# ESD_FINAL_SCHEMATICS2.net
KiCad netlist of a schematic drawn in EAGLE
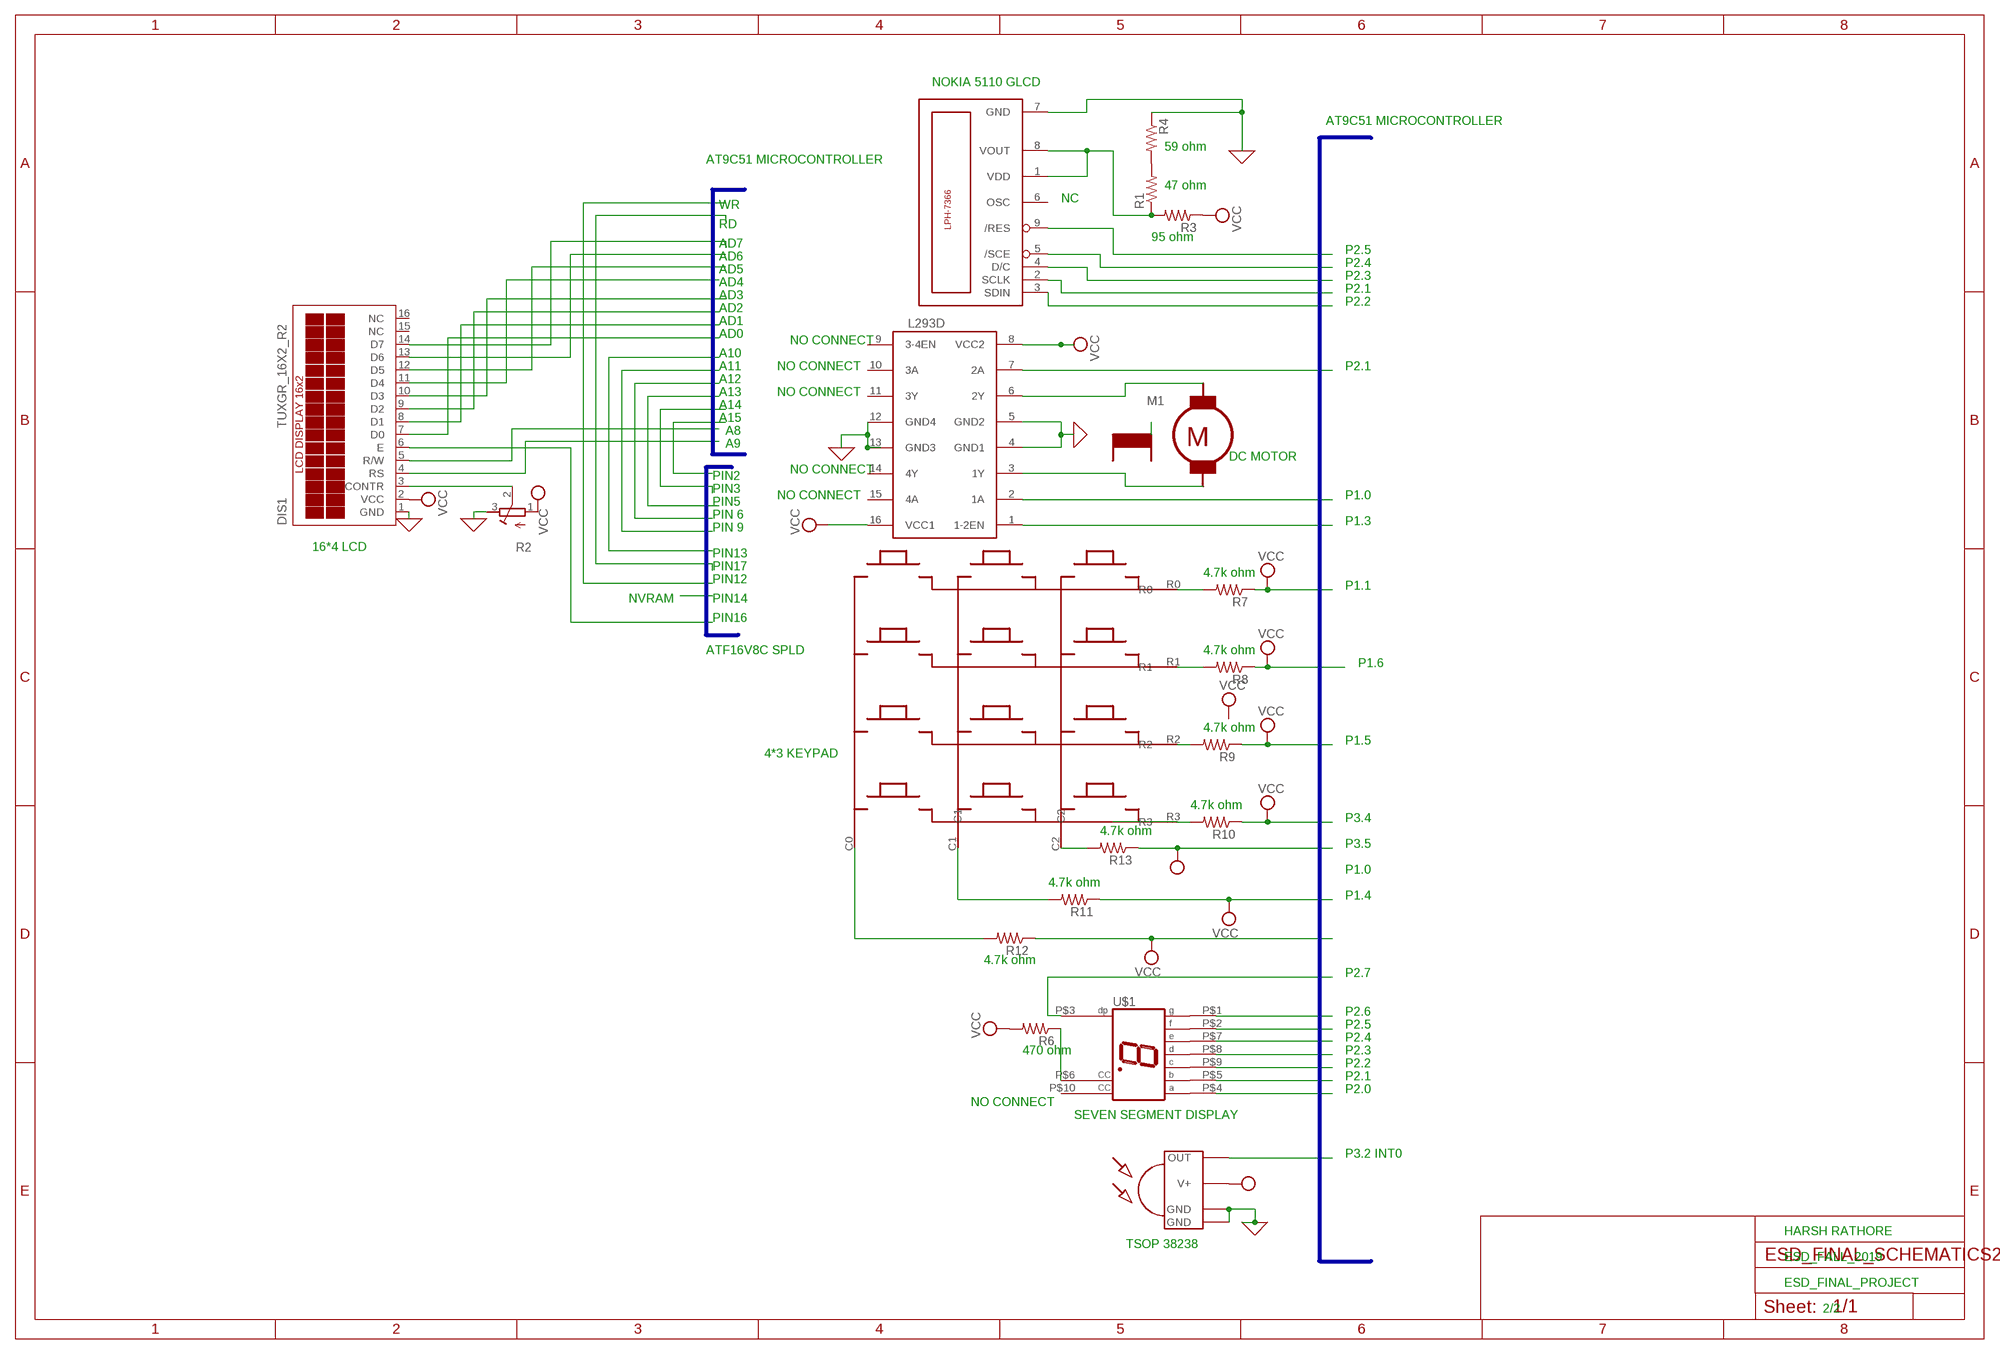
[diagram p0: schematic, sheet 1]

(export (version "E")
  (design (tool "Eeschema 10.0.6"))
  (components
    (comp (ref "DIS1")
      (value "TUXGR_16X2_R2")
      (footprint "eagle-import:TUXGR_16X2_R2")
      (libsource (lib "eagle-import") (part "TUXGR_16X2_R2"))
    )
    (comp (ref "IC1")
      (value "L293D")
      (footprint "eagle-import:DIL16")
      (libsource (lib "eagle-import") (part "L293D"))
    )
    (comp (ref "KP1")
      (value "KEYPAD")
      (footprint "eagle-import:KEYPAD")
      (libsource (lib "eagle-import") (part "KEYPAD"))
    )
    (comp (ref "LCD3")
      (value "LPH-7366")
      (footprint "eagle-import:LPH-7366")
      (libsource (lib "eagle-import") (part "LPH-7366"))
    )
    (comp (ref "M1")
      (value "MOTOR_DC_2_XL")
      (footprint "eagle-import:4PIN")
      (libsource (lib "eagle-import") (part "MOTOR_DC_2_XL"))
    )
    (comp (ref "R1")
      (value "R-US_0204/2V")
      (footprint "eagle-import:0204V")
      (libsource (lib "eagle-import") (part "R-US_0204/2V"))
    )
    (comp (ref "R2")
      (value "R-TRIMM4G/J")
      (footprint "eagle-import:RTRIM4G_J")
      (libsource (lib "eagle-import") (part "R-TRIMM4G/J"))
    )
    (comp (ref "R3")
      (value "R-US_0204/2V")
      (footprint "eagle-import:0204V")
      (libsource (lib "eagle-import") (part "R-US_0204/2V"))
    )
    (comp (ref "R4")
      (value "R-US_0204/2V")
      (footprint "eagle-import:0204V")
      (libsource (lib "eagle-import") (part "R-US_0204/2V"))
    )
    (comp (ref "R6")
      (value "R-US_0204/2V")
      (footprint "eagle-import:0204V")
      (libsource (lib "eagle-import") (part "R-US_0204/2V"))
    )
    (comp (ref "R7")
      (value "R-US_0204/2V")
      (footprint "eagle-import:0204V")
      (libsource (lib "eagle-import") (part "R-US_0204/2V"))
    )
    (comp (ref "R8")
      (value "R-US_0204/2V")
      (footprint "eagle-import:0204V")
      (libsource (lib "eagle-import") (part "R-US_0204/2V"))
    )
    (comp (ref "R9")
      (value "R-US_0204/2V")
      (footprint "eagle-import:0204V")
      (libsource (lib "eagle-import") (part "R-US_0204/2V"))
    )
    (comp (ref "R10")
      (value "R-US_0204/2V")
      (footprint "eagle-import:0204V")
      (libsource (lib "eagle-import") (part "R-US_0204/2V"))
    )
    (comp (ref "R11")
      (value "R-US_0204/2V")
      (footprint "eagle-import:0204V")
      (libsource (lib "eagle-import") (part "R-US_0204/2V"))
    )
    (comp (ref "R12")
      (value "R-US_0204/2V")
      (footprint "eagle-import:0204V")
      (libsource (lib "eagle-import") (part "R-US_0204/2V"))
    )
    (comp (ref "R13")
      (value "R-US_0204/2V")
      (footprint "eagle-import:0204V")
      (libsource (lib "eagle-import") (part "R-US_0204/2V"))
    )
    (comp (ref "U$1")
      (value "JUMBOLED")
      (footprint "eagle-import:JUMBOLED")
      (libsource (lib "eagle-import") (part "JUMBOLED"))
    )
    (comp (ref "U$2")
      (value "TSOP62XX")
      (footprint "eagle-import:TSOP62XX")
      (libsource (lib "eagle-import") (part "TSOP62XX"))
    )
  )
  (nets
    (net (code "1") (name "GND") (class "Default")
      (node (ref "DIS1") (pin "1") (pinfunction "GND_1") (pintype "power_in"))
      (node (ref "IC1") (pin "12") (pinfunction "GND4_12") (pintype "power_in"))
      (node (ref "IC1") (pin "13") (pinfunction "GND3_13") (pintype "power_in"))
      (node (ref "IC1") (pin "4") (pinfunction "GND1_4") (pintype "power_in"))
      (node (ref "IC1") (pin "5") (pinfunction "GND2_5") (pintype "power_in"))
      (node (ref "LCD3") (pin "7") (pinfunction "GND_7") (pintype "power_in"))
      (node (ref "R2") (pin "3") (pinfunction "E_3") (pintype "passive"))
      (node (ref "R4") (pin "1") (pinfunction "1_1") (pintype "passive"))
      (node (ref "U$2") (pin "1") (pinfunction "GND_1") (pintype "bidirectional"))
      (node (ref "U$2") (pin "2") (pinfunction "GND_2") (pintype "bidirectional"))
    )
    (net (code "2") (name "Net-(DIS1-CONTR)") (class "Default")
      (node (ref "DIS1") (pin "3") (pinfunction "CONTR_3") (pintype "input"))
      (node (ref "R2") (pin "2") (pinfunction "S_2") (pintype "passive"))
    )
    (net (code "3") (name "Net-(IC1-1Y)") (class "Default")
      (node (ref "IC1") (pin "3") (pinfunction "1Y_3") (pintype "output"))
      (node (ref "M1") (pin "1") (pinfunction "1_1") (pintype "passive"))
    )
    (net (code "4") (name "Net-(IC1-2Y)") (class "Default")
      (node (ref "IC1") (pin "6") (pinfunction "2Y_6") (pintype "output"))
      (node (ref "M1") (pin "2") (pinfunction "2_2") (pintype "passive"))
    )
    (net (code "5") (name "Net-(KP1-PadC0)") (class "Default")
      (node (ref "KP1") (pin "C0") (pinfunction "C0_C0") (pintype "bidirectional"))
      (node (ref "R12") (pin "2") (pinfunction "2_2") (pintype "passive"))
    )
    (net (code "6") (name "Net-(KP1-PadC1)") (class "Default")
      (node (ref "KP1") (pin "C1") (pinfunction "C1_C1") (pintype "bidirectional"))
      (node (ref "R11") (pin "2") (pinfunction "2_2") (pintype "passive"))
    )
    (net (code "7") (name "Net-(KP1-PadC2)") (class "Default")
      (node (ref "KP1") (pin "C2") (pinfunction "C2_C2") (pintype "bidirectional"))
      (node (ref "R13") (pin "2") (pinfunction "2_2") (pintype "passive"))
    )
    (net (code "8") (name "Net-(KP1-PadR0)") (class "Default")
      (node (ref "KP1") (pin "R0") (pinfunction "R0_R0") (pintype "bidirectional"))
      (node (ref "R7") (pin "2") (pinfunction "2_2") (pintype "passive"))
    )
    (net (code "9") (name "Net-(KP1-PadR1)") (class "Default")
      (node (ref "KP1") (pin "R1") (pinfunction "R1_R1") (pintype "bidirectional"))
      (node (ref "R8") (pin "2") (pinfunction "2_2") (pintype "passive"))
    )
    (net (code "10") (name "Net-(KP1-PadR2)") (class "Default")
      (node (ref "KP1") (pin "R2") (pinfunction "R2_R2") (pintype "bidirectional"))
      (node (ref "R9") (pin "2") (pinfunction "2_2") (pintype "passive"))
    )
    (net (code "11") (name "Net-(KP1-PadR3)") (class "Default")
      (node (ref "KP1") (pin "R3") (pinfunction "R3_R3") (pintype "bidirectional"))
      (node (ref "R10") (pin "2") (pinfunction "2_2") (pintype "passive"))
    )
    (net (code "12") (name "Net-(LCD3-VDD)") (class "Default")
      (node (ref "LCD3") (pin "1") (pinfunction "VDD_1") (pintype "power_in"))
      (node (ref "LCD3") (pin "8") (pinfunction "VOUT_8") (pintype "passive"))
      (node (ref "R1") (pin "1") (pinfunction "1_1") (pintype "passive"))
      (node (ref "R3") (pin "2") (pinfunction "2_2") (pintype "passive"))
    )
    (net (code "13") (name "Net-(R1-Pad2)") (class "Default")
      (node (ref "R1") (pin "2") (pinfunction "2_2") (pintype "passive"))
      (node (ref "R4") (pin "2") (pinfunction "2_2") (pintype "passive"))
    )
    (net (code "14") (name "Net-(R6-Pad1)") (class "Default")
      (node (ref "R6") (pin "1") (pinfunction "1_1") (pintype "passive"))
      (node (ref "U$1") (pin "P$6") (pinfunction "CC_P$6") (pintype "passive"))
    )
    (net (code "15") (name "VCC") (class "Default")
      (node (ref "DIS1") (pin "2") (pinfunction "VCC_2") (pintype "power_in"))
      (node (ref "IC1") (pin "16") (pinfunction "VCC1_16") (pintype "power_in"))
      (node (ref "IC1") (pin "8") (pinfunction "VCC2_8") (pintype "power_in"))
      (node (ref "R10") (pin "1") (pinfunction "1_1") (pintype "passive"))
      (node (ref "R11") (pin "1") (pinfunction "1_1") (pintype "passive"))
      (node (ref "R12") (pin "1") (pinfunction "1_1") (pintype "passive"))
      (node (ref "R13") (pin "1") (pinfunction "1_1") (pintype "passive"))
      (node (ref "R2") (pin "1") (pinfunction "A_1") (pintype "passive"))
      (node (ref "R3") (pin "1") (pinfunction "1_1") (pintype "passive"))
      (node (ref "R6") (pin "2") (pinfunction "2_2") (pintype "passive"))
      (node (ref "R7") (pin "1") (pinfunction "1_1") (pintype "passive"))
      (node (ref "R8") (pin "1") (pinfunction "1_1") (pintype "passive"))
      (node (ref "R9") (pin "1") (pinfunction "1_1") (pintype "passive"))
      (node (ref "U$2") (pin "3") (pinfunction "V+_3") (pintype "bidirectional"))
    )
    (net (code "16") (name "unconnected-(DIS1-D0-Pad7)") (class "Default")
      (node (ref "DIS1") (pin "7") (pinfunction "D0_7") (pintype "input"))
    )
    (net (code "17") (name "unconnected-(DIS1-D1-Pad8)") (class "Default")
      (node (ref "DIS1") (pin "8") (pinfunction "D1_8") (pintype "input"))
    )
    (net (code "18") (name "unconnected-(DIS1-D2-Pad9)") (class "Default")
      (node (ref "DIS1") (pin "9") (pinfunction "D2_9") (pintype "input"))
    )
    (net (code "19") (name "unconnected-(DIS1-D3-Pad10)") (class "Default")
      (node (ref "DIS1") (pin "10") (pinfunction "D3_10") (pintype "input"))
    )
    (net (code "20") (name "unconnected-(DIS1-D4-Pad11)") (class "Default")
      (node (ref "DIS1") (pin "11") (pinfunction "D4_11") (pintype "input"))
    )
    (net (code "21") (name "unconnected-(DIS1-D5-Pad12)") (class "Default")
      (node (ref "DIS1") (pin "12") (pinfunction "D5_12") (pintype "input"))
    )
    (net (code "22") (name "unconnected-(DIS1-D6-Pad13)") (class "Default")
      (node (ref "DIS1") (pin "13") (pinfunction "D6_13") (pintype "input"))
    )
    (net (code "23") (name "unconnected-(DIS1-D7-Pad14)") (class "Default")
      (node (ref "DIS1") (pin "14") (pinfunction "D7_14") (pintype "input"))
    )
    (net (code "24") (name "unconnected-(DIS1-E-Pad6)") (class "Default")
      (node (ref "DIS1") (pin "6") (pinfunction "E_6") (pintype "input"))
    )
    (net (code "25") (name "unconnected-(DIS1-NC-Pad15)") (class "Default")
      (node (ref "DIS1") (pin "15") (pinfunction "NC_15") (pintype "no_connect"))
    )
    (net (code "26") (name "unconnected-(DIS1-NC-Pad16)") (class "Default")
      (node (ref "DIS1") (pin "16") (pinfunction "NC_16") (pintype "no_connect"))
    )
    (net (code "27") (name "unconnected-(DIS1-RS-Pad4)") (class "Default")
      (node (ref "DIS1") (pin "4") (pinfunction "RS_4") (pintype "input"))
    )
    (net (code "28") (name "unconnected-(DIS1-R{slash}W-Pad5)") (class "Default")
      (node (ref "DIS1") (pin "5") (pinfunction "R/W_5") (pintype "input"))
    )
    (net (code "29") (name "unconnected-(IC1-1-2EN-Pad1)") (class "Default")
      (node (ref "IC1") (pin "1") (pinfunction "1-2EN_1") (pintype "input"))
    )
    (net (code "30") (name "unconnected-(IC1-1A-Pad2)") (class "Default")
      (node (ref "IC1") (pin "2") (pinfunction "1A_2") (pintype "input"))
    )
    (net (code "31") (name "unconnected-(IC1-2A-Pad7)") (class "Default")
      (node (ref "IC1") (pin "7") (pinfunction "2A_7") (pintype "input"))
    )
    (net (code "32") (name "unconnected-(IC1-3-4EN-Pad9)") (class "Default")
      (node (ref "IC1") (pin "9") (pinfunction "3-4EN_9") (pintype "input"))
    )
    (net (code "33") (name "unconnected-(IC1-3A-Pad10)") (class "Default")
      (node (ref "IC1") (pin "10") (pinfunction "3A_10") (pintype "input"))
    )
    (net (code "34") (name "unconnected-(IC1-3Y-Pad11)") (class "Default")
      (node (ref "IC1") (pin "11") (pinfunction "3Y_11") (pintype "output"))
    )
    (net (code "35") (name "unconnected-(IC1-4A-Pad15)") (class "Default")
      (node (ref "IC1") (pin "15") (pinfunction "4A_15") (pintype "input"))
    )
    (net (code "36") (name "unconnected-(IC1-4Y-Pad14)") (class "Default")
      (node (ref "IC1") (pin "14") (pinfunction "4Y_14") (pintype "output"))
    )
    (net (code "37") (name "unconnected-(LCD3-D{slash}C-Pad4)") (class "Default")
      (node (ref "LCD3") (pin "4") (pinfunction "D/C_4") (pintype "input"))
    )
    (net (code "38") (name "unconnected-(LCD3-OSC-Pad6)") (class "Default")
      (node (ref "LCD3") (pin "6") (pinfunction "OSC_6") (pintype "passive"))
    )
    (net (code "39") (name "unconnected-(LCD3-SCLK-Pad2)") (class "Default")
      (node (ref "LCD3") (pin "2") (pinfunction "SCLK_2") (pintype "input"))
    )
    (net (code "40") (name "unconnected-(LCD3-SDIN-Pad3)") (class "Default")
      (node (ref "LCD3") (pin "3") (pinfunction "SDIN_3") (pintype "input"))
    )
    (net (code "41") (name "unconnected-(LCD3-{slash}RES-Pad9)") (class "Default")
      (node (ref "LCD3") (pin "9") (pinfunction "/RES_9") (pintype "input"))
    )
    (net (code "42") (name "unconnected-(LCD3-{slash}SCE-Pad5)") (class "Default")
      (node (ref "LCD3") (pin "5") (pinfunction "/SCE_5") (pintype "input"))
    )
    (net (code "43") (name "unconnected-(M1-Pad3)") (class "Default")
      (node (ref "M1") (pin "3") (pinfunction "3_3") (pintype "passive"))
    )
    (net (code "44") (name "unconnected-(M1-Pad4)") (class "Default")
      (node (ref "M1") (pin "4") (pinfunction "4_4") (pintype "passive"))
    )
    (net (code "45") (name "unconnected-(U$1-A-PadP$4)") (class "Default")
      (node (ref "U$1") (pin "P$4") (pinfunction "A_P$4") (pintype "passive"))
    )
    (net (code "46") (name "unconnected-(U$1-B-PadP$5)") (class "Default")
      (node (ref "U$1") (pin "P$5") (pinfunction "B_P$5") (pintype "passive"))
    )
    (net (code "47") (name "unconnected-(U$1-C-PadP$9)") (class "Default")
      (node (ref "U$1") (pin "P$9") (pinfunction "C_P$9") (pintype "passive"))
    )
    (net (code "48") (name "unconnected-(U$1-CC-PadP$10)") (class "Default")
      (node (ref "U$1") (pin "P$10") (pinfunction "CC_P$10") (pintype "passive"))
    )
    (net (code "49") (name "unconnected-(U$1-D-PadP$8)") (class "Default")
      (node (ref "U$1") (pin "P$8") (pinfunction "D_P$8") (pintype "passive"))
    )
    (net (code "50") (name "unconnected-(U$1-DP-PadP$3)") (class "Default")
      (node (ref "U$1") (pin "P$3") (pinfunction "DP_P$3") (pintype "passive"))
    )
    (net (code "51") (name "unconnected-(U$1-E-PadP$7)") (class "Default")
      (node (ref "U$1") (pin "P$7") (pinfunction "E_P$7") (pintype "passive"))
    )
    (net (code "52") (name "unconnected-(U$1-F-PadP$2)") (class "Default")
      (node (ref "U$1") (pin "P$2") (pinfunction "F_P$2") (pintype "passive"))
    )
    (net (code "53") (name "unconnected-(U$1-G-PadP$1)") (class "Default")
      (node (ref "U$1") (pin "P$1") (pinfunction "G_P$1") (pintype "passive"))
    )
    (net (code "54") (name "unconnected-(U$2-OUT-Pad4)") (class "Default")
      (node (ref "U$2") (pin "4") (pinfunction "OUT_4") (pintype "bidirectional"))
    )
  )
)
